# Mcu_Control_Interface.net
KiCad netlist of a schematic drawn in Altium Designer
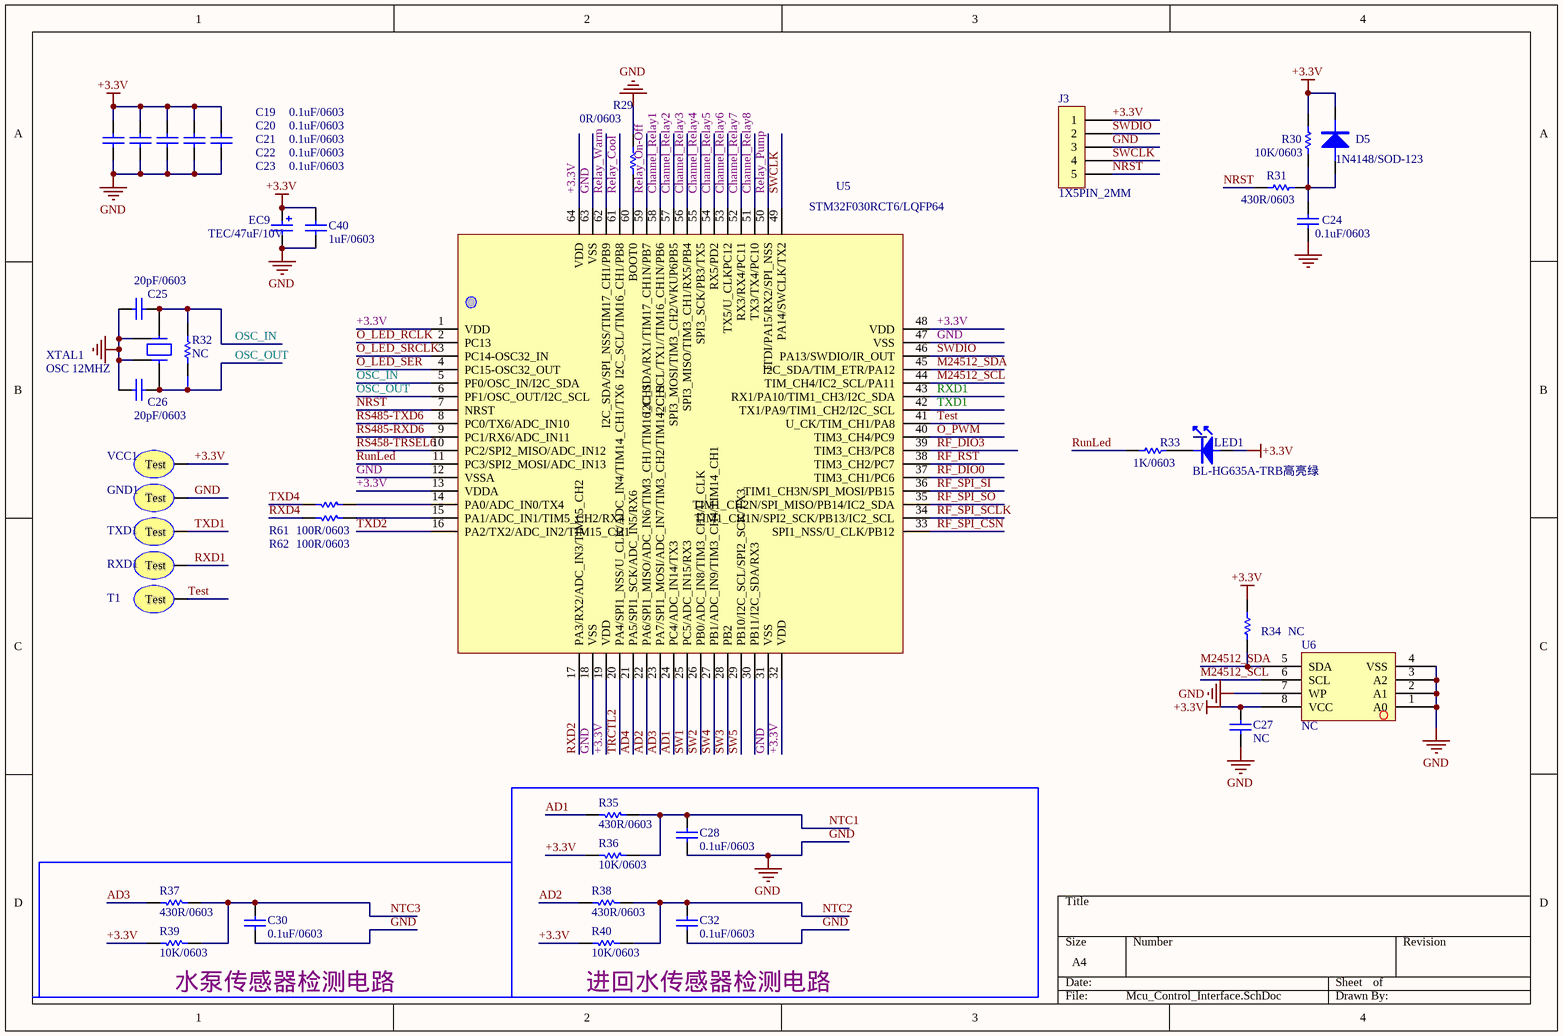
[diagram p0: Mcu_Control_Interface.SchDoc]

(export (version "E")
  (design (tool "Eeschema 10.0.6"))
  (components
    (comp (ref "C19")
      (value "0.1uF/0603")
      (footprint "CAP/SMT/0603C")
      (libsource (lib "Menred_原理图 封装库") (part "CAP/CAP/SMT/0603C"))
    )
    (comp (ref "C20")
      (value "0.1uF/0603")
      (footprint "CAP/SMT/0603C")
      (libsource (lib "Menred_原理图 封装库") (part "CAP/CAP/SMT/0603C"))
    )
    (comp (ref "C21")
      (value "0.1uF/0603")
      (footprint "CAP/SMT/0603C")
      (libsource (lib "Menred_原理图 封装库") (part "CAP/CAP/SMT/0603C"))
    )
    (comp (ref "C22")
      (value "0.1uF/0603")
      (footprint "CAP/SMT/0603C")
      (libsource (lib "Menred_原理图 封装库") (part "CAP/CAP/SMT/0603C"))
    )
    (comp (ref "C23")
      (value "0.1uF/0603")
      (footprint "CAP/SMT/0603C")
      (libsource (lib "Menred_原理图 封装库") (part "CAP/CAP/SMT/0603C"))
    )
    (comp (ref "C24")
      (value "0.1uF/0603")
      (footprint "CAP/SMT/0603C")
      (libsource (lib "Menred_原理图 封装库") (part "CAP/CAP/SMT/0603C"))
    )
    (comp (ref "C25")
      (value "20pF/0603")
      (footprint "CAP/SMT/0603C")
      (libsource (lib "Menred_原理图 封装库") (part "CAP/CAP/SMT/0603C"))
    )
    (comp (ref "C26")
      (value "20pF/0603")
      (footprint "CAP/SMT/0603C")
      (libsource (lib "Menred_原理图 封装库") (part "CAP/CAP/SMT/0603C"))
    )
    (comp (ref "C27")
      (value "NC")
      (footprint "CAP/SMT/0603C")
      (libsource (lib "Menred_原理图 封装库") (part "CAP/CAP/SMT/0603C"))
    )
    (comp (ref "C28")
      (value "0.1uF/0603")
      (footprint "CAP/SMT/0603C")
      (libsource (lib "Menred_原理图 封装库") (part "CAP/CAP/SMT/0603C"))
    )
    (comp (ref "C30")
      (value "0.1uF/0603")
      (footprint "CAP/SMT/0603C")
      (libsource (lib "Menred_原理图 封装库") (part "CAP/CAP/SMT/0603C"))
    )
    (comp (ref "C32")
      (value "0.1uF/0603")
      (footprint "CAP/SMT/0603C")
      (libsource (lib "Menred_原理图 封装库") (part "CAP/CAP/SMT/0603C"))
    )
    (comp (ref "C40")
      (value "1uF/0603")
      (footprint "CAP/SMT/0603C")
      (libsource (lib "Menred_原理图 封装库") (part "CAP/CAP/SMT/0603C"))
    )
    (comp (ref "D5")
      (value "1N4148/SOD-123")
      (footprint "D/SMT/SOD-123")
      (description "VR=75V T(-65-175)P(0.5W)VF=0.6V")
      (libsource (lib "Menred_原理图 封装库") (part "D/D/SMT/1N4148/SOD-123"))
    )
    (comp (ref "EC9")
      (value "TEC/47uF/10V")
      (footprint "CAP/SMT/TAJC476M010RNJ")
      (libsource (lib "Menred_原理图 封装库") (part "CAP/TEC/SMT/TAJC476M010RNJ"))
    )
    (comp (ref "GND1") (value "OTHER/TEST") (footprint "TEST") (libsource (lib "") (part "OTHER/TEST_1")))
    (comp (ref "J3")
      (value "1X5PIN_2MM")
      (footprint "CON/DIP/1×5PIN/2.0MM")
      (description "Connector")
      (libsource (lib "Menred_原理图 封装库") (part "CON/DIP/1X5PIN_2MM"))
    )
    (comp (ref "LED1")
      (value "BL-HG635A-TRB高亮绿")
      (footprint "D/SMT/LED/0805")
      (libsource (lib "Menred_原理图 封装库") (part "D/LED/SMT/BL-HG635A-TRB高亮绿/0805"))
    )
    (comp (ref "R29")
      (value "0R/0603")
      (footprint "0603R")
      (libsource (lib "Menred_原理图 封装库") (part "RES/RES/SMT/0603"))
    )
    (comp (ref "R30")
      (value "10K/0603")
      (footprint "0603R")
      (libsource (lib "电阻类器件") (part "RES/RES/SMT/0603"))
    )
    (comp (ref "R31")
      (value "430R/0603")
      (footprint "0603R")
      (libsource (lib "电阻类器件") (part "RES/RES/SMT/0603"))
    )
    (comp (ref "R32") (value "NC") (footprint "0603R") (libsource (lib "电阻类器件") (part "RES/RES/SMT/0603")))
    (comp (ref "R33")
      (value "1K/0603")
      (footprint "0603R")
      (libsource (lib "Menred_原理图 封装库") (part "RES/RES/SMT/0603"))
    )
    (comp (ref "R34")
      (value "NC")
      (footprint "0603R")
      (libsource (lib "Menred_原理图 封装库") (part "RES/RES/SMT/0603"))
    )
    (comp (ref "R35")
      (value "430R/0603")
      (footprint "0603R")
      (libsource (lib "Menred_原理图 封装库") (part "RES/RES/SMT/0603"))
    )
    (comp (ref "R36")
      (value "10K/0603")
      (footprint "0603R")
      (libsource (lib "Menred_原理图 封装库") (part "RES/RES/SMT/0603"))
    )
    (comp (ref "R37")
      (value "430R/0603")
      (footprint "0603R")
      (libsource (lib "Menred_原理图 封装库") (part "RES/RES/SMT/0603"))
    )
    (comp (ref "R38")
      (value "430R/0603")
      (footprint "0603R")
      (libsource (lib "Menred_原理图 封装库") (part "RES/RES/SMT/0603"))
    )
    (comp (ref "R39")
      (value "10K/0603")
      (footprint "0603R")
      (libsource (lib "Menred_原理图 封装库") (part "RES/RES/SMT/0603"))
    )
    (comp (ref "R40")
      (value "10K/0603")
      (footprint "0603R")
      (libsource (lib "Menred_原理图 封装库") (part "RES/RES/SMT/0603"))
    )
    (comp (ref "R61")
      (value "100R/0603")
      (footprint "0603R")
      (description "Resistor")
      (fields
        (field (name "MANUFACTURER") "Generic Components")
        (field (name "PUBLISHER") "Altium Hobart Technology Centre")
      )
      (libsource (lib "*") (part "Res1"))
    )
    (comp (ref "R62")
      (value "100R/0603")
      (footprint "0603R")
      (description "Resistor")
      (fields
        (field (name "MANUFACTURER") "Generic Components")
        (field (name "PUBLISHER") "Altium Hobart Technology Centre")
      )
      (libsource (lib "*") (part "Res1"))
    )
    (comp (ref "RXD1") (value "OTHER/TEST") (footprint "TEST") (libsource (lib "") (part "OTHER/TEST_1")))
    (comp (ref "T1")
      (value "OTHER/TEST")
      (footprint "TEST")
      (libsource (lib "Menred_原理图 封装库") (part "OTHER/TEST"))
    )
    (comp (ref "TXD1") (value "OTHER/TEST") (footprint "TEST") (libsource (lib "") (part "OTHER/TEST_1")))
    (comp (ref "U5")
      (value "STM32F030RCT6/LQFP64")
      (footprint "LQFP64")
      (libsource (lib "Menred_原理图 封装库") (part "MCU/SMT/STM32F030RCT6/LQFP64"))
    )
    (comp (ref "U6")
      (value "NC")
      (footprint "SOP-8")
      (description "512 Kbit serial I2C bus EEPROM with three Chip Enable lines")
      (libsource (lib "Menred_原理图 封装库") (part "IC/FLASH/SMT/M24512-RMN6TP/SO8"))
    )
    (comp (ref "VCC1") (value "OTHER/TEST") (footprint "TEST") (libsource (lib "") (part "OTHER/TEST_1")))
    (comp (ref "XTAL1")
      (value "OSC 12MHZ")
      (footprint "OSC/SMT/12M")
      (libsource (lib "Menred_原理图 封装库") (part "XTAL/SMT/OSC12MHZ-2"))
    )
  )
  (nets
    (net (code "1") (name "+3.3V") (class "Default")
      (node (ref "C19") (pin "2") (pinfunction "2_2") (pintype "passive"))
      (node (ref "C20") (pin "2") (pinfunction "2_2") (pintype "passive"))
      (node (ref "C21") (pin "2") (pinfunction "2_2") (pintype "passive"))
      (node (ref "C22") (pin "2") (pinfunction "2_2") (pintype "passive"))
      (node (ref "C23") (pin "2") (pinfunction "2_2") (pintype "passive"))
      (node (ref "C27") (pin "2") (pinfunction "2_2") (pintype "passive"))
      (node (ref "C40") (pin "2") (pinfunction "2_2") (pintype "passive"))
      (node (ref "D5") (pin "1") (pinfunction "K_1") (pintype "passive"))
      (node (ref "EC9") (pin "1") (pinfunction "1_1") (pintype "passive"))
      (node (ref "J3") (pin "1") (pinfunction "1_1") (pintype "passive"))
      (node (ref "LED1") (pin "2") (pinfunction "A_2") (pintype "passive"))
      (node (ref "R30") (pin "2") (pinfunction "2_2") (pintype "passive"))
      (node (ref "R34") (pin "1") (pinfunction "1_1") (pintype "passive"))
      (node (ref "R36") (pin "1") (pinfunction "1_1") (pintype "passive"))
      (node (ref "R39") (pin "1") (pinfunction "1_1") (pintype "passive"))
      (node (ref "R40") (pin "1") (pinfunction "1_1") (pintype "passive"))
      (node (ref "U5") (pin "1") (pinfunction "VDD_1") (pintype "passive"))
      (node (ref "U5") (pin "13") (pinfunction "VDDA_13") (pintype "passive"))
      (node (ref "U5") (pin "19") (pinfunction "VDD_19") (pintype "passive"))
      (node (ref "U5") (pin "32") (pinfunction "VDD_32") (pintype "passive"))
      (node (ref "U5") (pin "48") (pinfunction "VDD_48") (pintype "passive"))
      (node (ref "U5") (pin "64") (pinfunction "VDD_64") (pintype "passive"))
      (node (ref "U6") (pin "8") (pinfunction "VCC_8") (pintype "passive"))
      (node (ref "VCC1") (pin "1") (pinfunction "Test_1") (pintype "passive"))
    )
    (net (code "2") (name "/AD1") (class "Default")
      (node (ref "R35") (pin "1") (pinfunction "1_1") (pintype "passive"))
      (node (ref "U5") (pin "24") (pinfunction "PC4/ADC_IN14/TX3_24") (pintype "passive"))
    )
    (net (code "3") (name "/AD2") (class "Default")
      (node (ref "R38") (pin "1") (pinfunction "1_1") (pintype "passive"))
      (node (ref "U5") (pin "22") (pinfunction "PA6/SPI1_MISO/ADC_IN6/TIM3_CH1/TIM16_CH1_22") (pintype "passive"))
    )
    (net (code "4") (name "/AD3") (class "Default")
      (node (ref "R37") (pin "1") (pinfunction "1_1") (pintype "passive"))
      (node (ref "U5") (pin "23") (pinfunction "PA7/SPI1_MOSI/ADC_IN7/TIM3_CH2/TIM14_CH1_23") (pintype "passive"))
    )
    (net (code "5") (name "/AD4") (class "Default")
      (node (ref "U5") (pin "21") (pinfunction "PA5/SPI1_SCK/ADC_IN5/RX6_21") (pintype "passive"))
    )
    (net (code "6") (name "/Channel_Relay1") (class "Default")
      (node (ref "U5") (pin "58") (pinfunction "I2C_SCL/TX1//TIM16_CH1N/PB6_58") (pintype "passive"))
    )
    (net (code "7") (name "/Channel_Relay2") (class "Default")
      (node (ref "U5") (pin "57") (pinfunction "SPI3_MOSI/TIM3_CH2/WKUP6PB5_57") (pintype "passive"))
    )
    (net (code "8") (name "/Channel_Relay3") (class "Default")
      (node (ref "U5") (pin "56") (pinfunction "SPI3_MISO/TIM3_CH1/RX5/PB4_56") (pintype "passive"))
    )
    (net (code "9") (name "/Channel_Relay4") (class "Default")
      (node (ref "U5") (pin "55") (pinfunction "SPI3_SCK/PB3/TX5_55") (pintype "passive"))
    )
    (net (code "10") (name "/Channel_Relay5") (class "Default")
      (node (ref "U5") (pin "54") (pinfunction "RX5/PD2_54") (pintype "passive"))
    )
    (net (code "11") (name "/Channel_Relay6") (class "Default")
      (node (ref "U5") (pin "53") (pinfunction "TX5/U_CLKPC12_53") (pintype "passive"))
    )
    (net (code "12") (name "/Channel_Relay7") (class "Default")
      (node (ref "U5") (pin "52") (pinfunction "RX3/RX4/PC11_52") (pintype "passive"))
    )
    (net (code "13") (name "/Channel_Relay8") (class "Default")
      (node (ref "U5") (pin "51") (pinfunction "TX3/TX4/PC10_51") (pintype "passive"))
    )
    (net (code "14") (name "/M24512_SCL") (class "Default")
      (node (ref "U5") (pin "44") (pinfunction "TIM_CH4/IC2_SCL/PA11_44") (pintype "passive"))
      (node (ref "U6") (pin "6") (pinfunction "SCL_6") (pintype "passive"))
    )
    (net (code "15") (name "/M24512_SDA") (class "Default")
      (node (ref "R34") (pin "2") (pinfunction "2_2") (pintype "passive"))
      (node (ref "U5") (pin "45") (pinfunction "I2C_SDA/TIM_ETR/PA12_45") (pintype "passive"))
      (node (ref "U6") (pin "5") (pinfunction "SDA_5") (pintype "passive"))
    )
    (net (code "16") (name "/NRST") (class "Default")
      (node (ref "J3") (pin "5") (pinfunction "5_5") (pintype "passive"))
      (node (ref "R31") (pin "1") (pinfunction "1_1") (pintype "passive"))
      (node (ref "U5") (pin "7") (pinfunction "NRST_7") (pintype "passive"))
    )
    (net (code "17") (name "/NTC1") (class "Default")
      (node (ref "C28") (pin "2") (pinfunction "2_2") (pintype "passive"))
      (node (ref "R35") (pin "2") (pinfunction "2_2") (pintype "passive"))
      (node (ref "R36") (pin "2") (pinfunction "2_2") (pintype "passive"))
    )
    (net (code "18") (name "/NTC2") (class "Default")
      (node (ref "C32") (pin "2") (pinfunction "2_2") (pintype "passive"))
      (node (ref "R38") (pin "2") (pinfunction "2_2") (pintype "passive"))
      (node (ref "R40") (pin "2") (pinfunction "2_2") (pintype "passive"))
    )
    (net (code "19") (name "/NTC3") (class "Default")
      (node (ref "C30") (pin "2") (pinfunction "2_2") (pintype "passive"))
      (node (ref "R37") (pin "2") (pinfunction "2_2") (pintype "passive"))
      (node (ref "R39") (pin "2") (pinfunction "2_2") (pintype "passive"))
    )
    (net (code "20") (name "/OSC_IN") (class "Default")
      (node (ref "C25") (pin "1") (pinfunction "1_1") (pintype "passive"))
      (node (ref "R32") (pin "2") (pinfunction "2_2") (pintype "passive"))
      (node (ref "U5") (pin "5") (pinfunction "PF0/OSC_IN/I2C_SDA_5") (pintype "passive"))
      (node (ref "XTAL1") (pin "3") (pinfunction "3_3") (pintype "passive"))
    )
    (net (code "21") (name "/OSC_OUT") (class "Default")
      (node (ref "C26") (pin "1") (pinfunction "1_1") (pintype "passive"))
      (node (ref "R32") (pin "1") (pinfunction "1_1") (pintype "passive"))
      (node (ref "U5") (pin "6") (pinfunction "PF1/OSC_OUT/I2C_SCL_6") (pintype "passive"))
      (node (ref "XTAL1") (pin "1") (pinfunction "1_1") (pintype "passive"))
    )
    (net (code "22") (name "/O_LED_RCLK") (class "Default")
      (node (ref "U5") (pin "2") (pinfunction "PC13_2") (pintype "passive"))
    )
    (net (code "23") (name "/O_LED_SER") (class "Default")
      (node (ref "U5") (pin "4") (pinfunction "PC15-OSC32_OUT_4") (pintype "passive"))
    )
    (net (code "24") (name "/O_LED_SRCLK") (class "Default")
      (node (ref "U5") (pin "3") (pinfunction "PC14-OSC32_IN_3") (pintype "passive"))
    )
    (net (code "25") (name "/O_PWM") (class "Default")
      (node (ref "U5") (pin "40") (pinfunction "TIM3_CH4/PC9_40") (pintype "passive"))
    )
    (net (code "26") (name "/RF_DIO0") (class "Default")
      (node (ref "U5") (pin "37") (pinfunction "TIM3_CH1/PC6_37") (pintype "passive"))
    )
    (net (code "27") (name "/RF_DIO3") (class "Default")
      (node (ref "U5") (pin "39") (pinfunction "TIM3_CH3/PC8_39") (pintype "passive"))
    )
    (net (code "28") (name "/RF_RST") (class "Default")
      (node (ref "U5") (pin "38") (pinfunction "TIM3_CH2/PC7_38") (pintype "passive"))
    )
    (net (code "29") (name "/RF_SPI_CSN") (class "Default")
      (node (ref "U5") (pin "33") (pinfunction "SPI1_NSS/U_CLK/PB12_33") (pintype "passive"))
    )
    (net (code "30") (name "/RF_SPI_SCLK") (class "Default")
      (node (ref "U5") (pin "34") (pinfunction "TIM1_CH1N/SPI2_SCK/PB13/IC2_SCL_34") (pintype "passive"))
    )
    (net (code "31") (name "/RF_SPI_SI") (class "Default")
      (node (ref "U5") (pin "36") (pinfunction "TIM1_CH3N/SPI_MOSI/PB15_36") (pintype "passive"))
    )
    (net (code "32") (name "/RF_SPI_SO") (class "Default")
      (node (ref "U5") (pin "35") (pinfunction "TIM1_CH2N/SPI_MISO/PB14/IC2_SDA_35") (pintype "passive"))
    )
    (net (code "33") (name "/RS458-TRSEL6") (class "Default")
      (node (ref "U5") (pin "10") (pinfunction "PC2/SPI2_MISO/ADC_IN12_10") (pintype "passive"))
    )
    (net (code "34") (name "/RS485-RXD6") (class "Default")
      (node (ref "U5") (pin "9") (pinfunction "PC1/RX6/ADC_IN11_9") (pintype "passive"))
    )
    (net (code "35") (name "/RS485-TXD6") (class "Default")
      (node (ref "U5") (pin "8") (pinfunction "PC0/TX6/ADC_IN10_8") (pintype "passive"))
    )
    (net (code "36") (name "/RXD1") (class "Default")
      (node (ref "RXD1") (pin "1") (pinfunction "Test_1") (pintype "passive"))
      (node (ref "U5") (pin "43") (pinfunction "RX1/PA10/TIM1_CH3/I2C_SDA_43") (pintype "passive"))
    )
    (net (code "37") (name "/RXD2") (class "Default")
      (node (ref "U5") (pin "17") (pinfunction "PA3/RX2/ADC_IN3/TIM15_CH2_17") (pintype "passive"))
    )
    (net (code "38") (name "/RXD4") (class "Default")
      (node (ref "R62") (pin "2") (pinfunction "2_2") (pintype "passive"))
    )
    (net (code "39") (name "/Relay_Cool") (class "Default")
      (node (ref "U5") (pin "61") (pinfunction "I2C_SCL/TIM16_CH1/PB8_61") (pintype "passive"))
    )
    (net (code "40") (name "/Relay_On-Off") (class "Default")
      (node (ref "U5") (pin "59") (pinfunction "I2C_SDA/RX1/TIM17_CH1N/PB7_59") (pintype "passive"))
    )
    (net (code "41") (name "/Relay_Pump") (class "Default")
      (node (ref "U5") (pin "50") (pinfunction "JTDI/PA15/RX2/SPI_NSS_50") (pintype "passive"))
    )
    (net (code "42") (name "/Relay_Warm") (class "Default")
      (node (ref "U5") (pin "62") (pinfunction "I2C_SDA/SPI_NSS/TIM17_CH1/PB9_62") (pintype "passive"))
    )
    (net (code "43") (name "/RunLed") (class "Default")
      (node (ref "R33") (pin "1") (pinfunction "1_1") (pintype "passive"))
      (node (ref "U5") (pin "11") (pinfunction "PC3/SPI2_MOSI/ADC_IN13_11") (pintype "passive"))
    )
    (net (code "44") (name "/SW1") (class "Default")
      (node (ref "U5") (pin "25") (pinfunction "PC5/ADC_IN15/RX3_25") (pintype "passive"))
    )
    (net (code "45") (name "/SW2") (class "Default")
      (node (ref "U5") (pin "26") (pinfunction "PB0/ADC_IN8/TIM3_CH3/U_CLK_26") (pintype "passive"))
    )
    (net (code "46") (name "/SW3") (class "Default")
      (node (ref "U5") (pin "28") (pinfunction "PB2_28") (pintype "passive"))
    )
    (net (code "47") (name "/SW4") (class "Default")
      (node (ref "U5") (pin "27") (pinfunction "PB1/ADC_IN9/TIM3_CH4/TIM14_CH1_27") (pintype "passive"))
    )
    (net (code "48") (name "/SW5") (class "Default")
      (node (ref "U5") (pin "29") (pinfunction "PB10/I2C_SCL/SPI2_SCK/TX3_29") (pintype "passive"))
    )
    (net (code "49") (name "/SWCLK") (class "Default")
      (node (ref "J3") (pin "4") (pinfunction "4_4") (pintype "passive"))
      (node (ref "U5") (pin "49") (pinfunction "PA14/SWCLK/TX2_49") (pintype "passive"))
    )
    (net (code "50") (name "/SWDIO") (class "Default")
      (node (ref "J3") (pin "2") (pinfunction "2_2") (pintype "passive"))
      (node (ref "U5") (pin "46") (pinfunction "PA13/SWDIO/IR_OUT_46") (pintype "passive"))
    )
    (net (code "51") (name "/TRCTL2") (class "Default")
      (node (ref "U5") (pin "20") (pinfunction "PA4/SPI1_NSS/U_CLK/ADC_IN4/TIM14_CH1/TX6_20") (pintype "passive"))
    )
    (net (code "52") (name "/TXD1") (class "Default")
      (node (ref "TXD1") (pin "1") (pinfunction "Test_1") (pintype "passive"))
      (node (ref "U5") (pin "42") (pinfunction "TX1/PA9/TIM1_CH2/I2C_SCL_42") (pintype "passive"))
    )
    (net (code "53") (name "/TXD2") (class "Default")
      (node (ref "U5") (pin "16") (pinfunction "PA2/TX2/ADC_IN2/TIM15_CH1_16") (pintype "passive"))
    )
    (net (code "54") (name "/TXD4") (class "Default")
      (node (ref "R61") (pin "2") (pinfunction "2_2") (pintype "passive"))
    )
    (net (code "55") (name "/Test") (class "Default")
      (node (ref "T1") (pin "1") (pinfunction "Test_1") (pintype "passive"))
      (node (ref "U5") (pin "41") (pinfunction "U_CK/TIM_CH1/PA8_41") (pintype "passive"))
    )
    (net (code "58") (name "GND") (class "Default")
      (node (ref "C19") (pin "1") (pinfunction "1_1") (pintype "passive"))
      (node (ref "C20") (pin "1") (pinfunction "1_1") (pintype "passive"))
      (node (ref "C21") (pin "1") (pinfunction "1_1") (pintype "passive"))
      (node (ref "C22") (pin "1") (pinfunction "1_1") (pintype "passive"))
      (node (ref "C23") (pin "1") (pinfunction "1_1") (pintype "passive"))
      (node (ref "C24") (pin "1") (pinfunction "1_1") (pintype "passive"))
      (node (ref "C25") (pin "2") (pinfunction "2_2") (pintype "passive"))
      (node (ref "C26") (pin "2") (pinfunction "2_2") (pintype "passive"))
      (node (ref "C27") (pin "1") (pinfunction "1_1") (pintype "passive"))
      (node (ref "C28") (pin "1") (pinfunction "1_1") (pintype "passive"))
      (node (ref "C30") (pin "1") (pinfunction "1_1") (pintype "passive"))
      (node (ref "C32") (pin "1") (pinfunction "1_1") (pintype "passive"))
      (node (ref "C40") (pin "1") (pinfunction "1_1") (pintype "passive"))
      (node (ref "EC9") (pin "2") (pinfunction "2_2") (pintype "passive"))
      (node (ref "GND1") (pin "1") (pinfunction "Test_1") (pintype "passive"))
      (node (ref "J3") (pin "3") (pinfunction "3_3") (pintype "passive"))
      (node (ref "R29") (pin "2") (pinfunction "2_2") (pintype "passive"))
      (node (ref "U5") (pin "12") (pinfunction "VSSA_12") (pintype "passive"))
      (node (ref "U5") (pin "18") (pinfunction "VSS_18") (pintype "passive"))
      (node (ref "U5") (pin "31") (pinfunction "VSS_31") (pintype "passive"))
      (node (ref "U5") (pin "47") (pinfunction "VSS_47") (pintype "passive"))
      (node (ref "U5") (pin "63") (pinfunction "VSS_63") (pintype "passive"))
      (node (ref "U6") (pin "1") (pinfunction "A0_1") (pintype "passive"))
      (node (ref "U6") (pin "2") (pinfunction "A1_2") (pintype "passive"))
      (node (ref "U6") (pin "3") (pinfunction "A2_3") (pintype "passive"))
      (node (ref "U6") (pin "4") (pinfunction "VSS_4") (pintype "passive"))
      (node (ref "U6") (pin "7") (pinfunction "WP_7") (pintype "passive"))
      (node (ref "XTAL1") (pin "2") (pinfunction "2_2") (pintype "passive"))
      (node (ref "XTAL1") (pin "4") (pinfunction "4_4") (pintype "passive"))
    )
    (net (code "59") (name "Net-(D5-A)") (class "Default")
      (node (ref "C24") (pin "2") (pinfunction "2_2") (pintype "passive"))
      (node (ref "D5") (pin "2") (pinfunction "A_2") (pintype "passive"))
      (node (ref "R30") (pin "1") (pinfunction "1_1") (pintype "passive"))
      (node (ref "R31") (pin "2") (pinfunction "2_2") (pintype "passive"))
    )
    (net (code "60") (name "Net-(LED1-K)") (class "Default")
      (node (ref "LED1") (pin "1") (pinfunction "K_1") (pintype "passive"))
      (node (ref "R33") (pin "2") (pinfunction "2_2") (pintype "passive"))
    )
    (net (code "61") (name "Net-(U5-BOOT0)") (class "Default")
      (node (ref "R29") (pin "1") (pinfunction "1_1") (pintype "passive"))
      (node (ref "U5") (pin "60") (pinfunction "BOOT0_60") (pintype "passive"))
    )
    (net (code "62") (name "Net-(U5-PA0{slash}ADC_IN0{slash}TX4)") (class "Default")
      (node (ref "R61") (pin "1") (pinfunction "1_1") (pintype "passive"))
      (node (ref "U5") (pin "14") (pinfunction "PA0/ADC_IN0/TX4_14") (pintype "passive"))
    )
    (net (code "63") (name "Net-(U5-PA1{slash}ADC_IN1{slash}TIM5_CH2{slash}RX4)") (class "Default")
      (node (ref "R62") (pin "1") (pinfunction "1_1") (pintype "passive"))
      (node (ref "U5") (pin "15") (pinfunction "PA1/ADC_IN1/TIM5_CH2/RX4_15") (pintype "passive"))
    )
    (net (code "64") (name "unconnected-(U5-PB11{slash}I2C_SDA{slash}RX3-Pad30)") (class "Default")
      (node (ref "U5") (pin "30") (pinfunction "PB11/I2C_SDA/RX3_30") (pintype "passive"))
    )
  )
)
